# Carte_OPB.net
KiCad netlist of a schematic drawn in Altium Designer
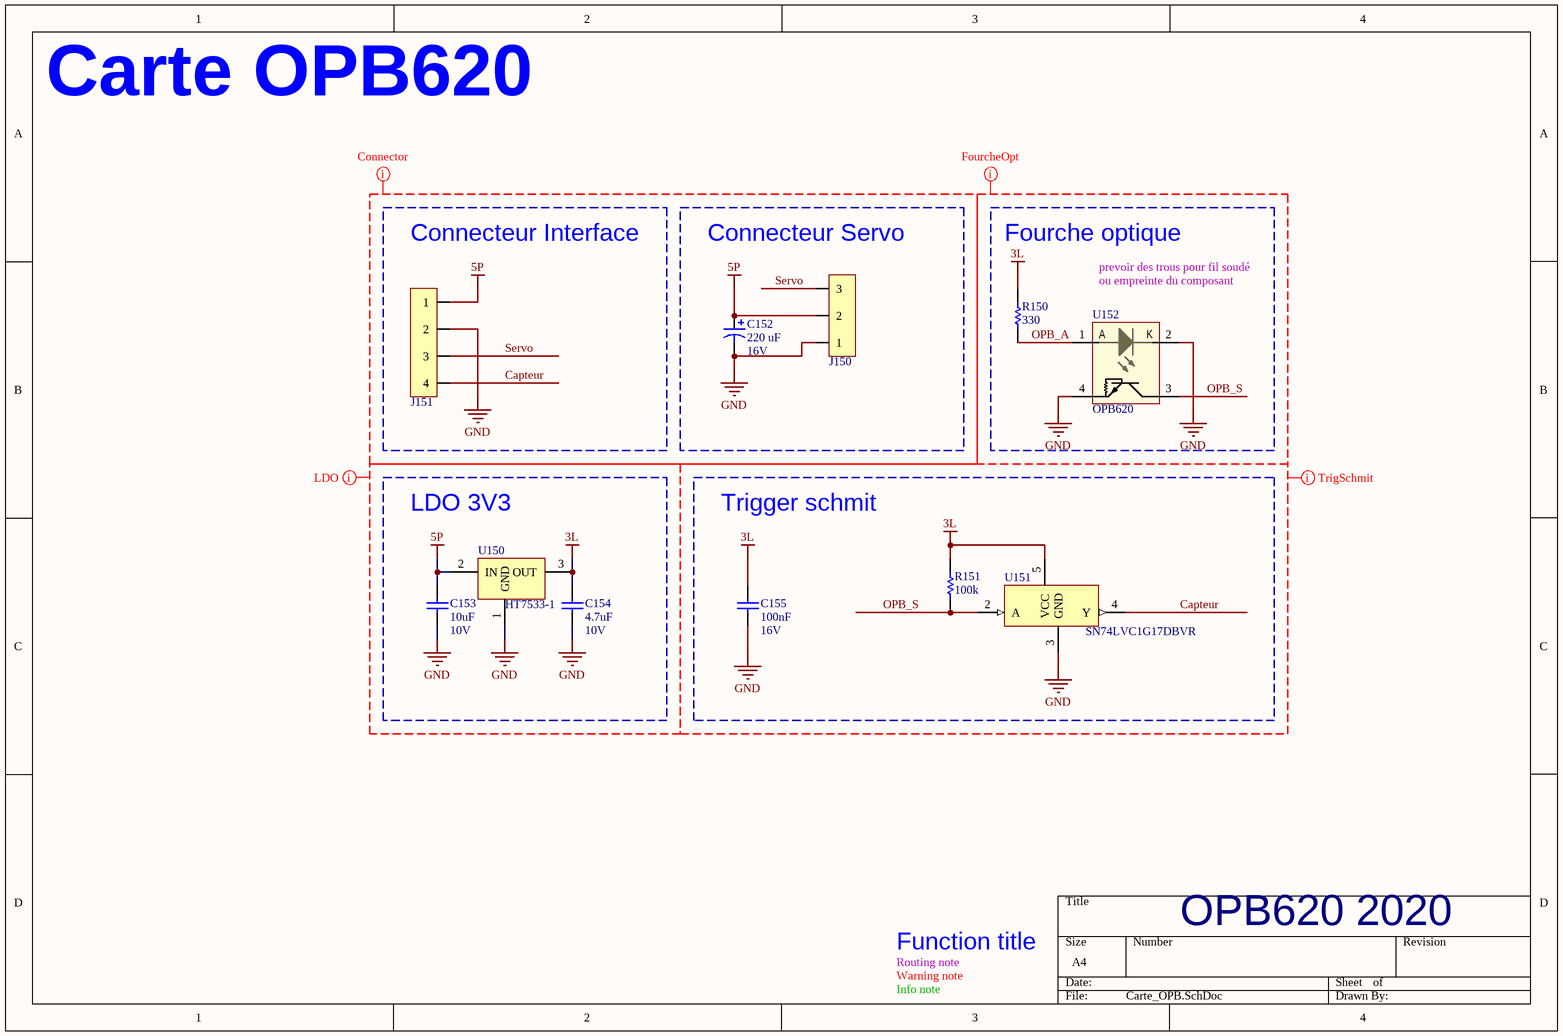
[diagram p0: Carte_OPB.SchDoc]

(export (version "E")
  (design (tool "Eeschema 10.0.6"))
  (components
    (comp (ref "C152")
      (value "220 uF")
      (footprint "WCAP-ATG8_6.3x11x2.5x0.5")
      (description "CAP Alu 220 UF 20% 16 V")
      (fields
        (field (name "MANUFACTURER") "Wurth Elektronik")
        (field (name "MANUFACTURER PART NUMBER") "860010373010")
        (field (name "RATEDVOLTAGE") "16V")
      )
      (libsource (lib "Condensateur") (part "WCAP-ATG8, 860010373010"))
    )
    (comp (ref "C153")
      (value "10uF")
      (footprint "WCAP-CSGP_0805, 2x1.25x1.25")
      (description "CAP CER 10uF 10V X7R 0805")
      (fields
        (field (name "RATEDVOLTAGE") "10V")
        (field (name "MANUFACTURER") "Wurth Elektronik")
        (field (name "MANUFACTURER PART NUMBER") "885012207026")
      )
      (libsource (lib "Condensateur") (part "WCAP-CSGP, 885012207026"))
    )
    (comp (ref "C154")
      (value "4.7uF")
      (footprint "WCAP-CSGP_0603, 1.6x0.8x0.8")
      (description "CAP CER 4.7UF 10V X5R 0603")
      (fields
        (field (name "RATEDVOLTAGE") "10V")
        (field (name "MANUFACTURER") "Wurth Elektronik")
        (field (name "MANUFACTURER PART NUMBER") "885012106012")
      )
      (libsource (lib "Condensateur") (part "WCAP-CSGP, 885012106012"))
    )
    (comp (ref "C155")
      (value "100nF")
      (footprint "WCAP-CSGP_0402, 1x0.5x0.5")
      (description "CAP CER 100nF 16V X7R 0402")
      (fields
        (field (name "RATEDVOLTAGE") "16V")
        (field (name "MANUFACTURER") "Wurth Elektronik")
        (field (name "MANUFACTURER PART NUMBER") "885012205037")
      )
      (libsource (lib "Condensateur") (part "WCAP-CSGP, 885012205037"))
    )
    (comp (ref "J150")
      (value "22-03-2031")
      (footprint "22-03-2031")
      (description "CONN HEADER VERT 3POS 2.54MM")
      (fields (field (name "MANUFACTURER") "MOLEX"))
      (libsource (lib "Connecteurs") (part "22-03-2031"))
    )
    (comp (ref "J151")
      (value "22-03-2041")
      (footprint "22-03-2041")
      (description "CONN HEADER VERT 4POS 2.54MM")
      (fields (field (name "MANUFACTURER") "MOLEX"))
      (libsource (lib "Connecteurs") (part "22-03-2041"))
    )
    (comp (ref "R150")
      (value "330")
      (footprint "RESC1005X04N")
      (description "RES SMD 330 OHM 1% 1/16W 0402")
      (fields (field (name "POWER") "63mW") (field (name "MANUFACTURER") "Yageo"))
      (libsource (lib "Resistance") (part "RC0402FR-07330RL"))
    )
    (comp (ref "R151")
      (value "100k")
      (footprint "RESC1005X04N")
      (description "RES SMD 100K OHM 1% 1/16W 0402")
      (fields (field (name "POWER") "63mW") (field (name "MANUFACTURER") "Yageo"))
      (libsource (lib "Resistance") (part "RC0402FR-07100KL"))
    )
    (comp (ref "U150")
      (value "HT7533-1")
      (footprint "SOT89-150P350X160-3N")
      (description "LDO 3.3V 100mA SOT89")
      (fields (field (name "MANUFACTURER") "Holtek"))
      (libsource (lib "Alimentation") (part "HT7533-1"))
    )
    (comp (ref "U151")
      (value "SN74LVC1G17DBVR")
      (footprint "SOT23_95P280X145-5N")
      (description "IC BUF NON-INVERT 5.5V SOT23-5")
      (fields (field (name "MANUFACTURER") "TEXAS INSTRUMENTS"))
      (libsource (lib "CI") (part "SN74LVC1G17DBVR"))
    )
    (comp (ref "U152")
      (value "OPB620")
      (footprint "OPB620")
      (description "SENSOR OPT SLOT TRANS W/RES PCB")
      (fields (field (name "MANUFACTURER") "TT ELECTRONICS"))
      (libsource (lib "Opto") (part "OPB620"))
    )
  )
  (nets
    (net (code "1") (name "/Capteur") (class "Default")
      (node (ref "J151") (pin "4") (pinfunction "4_4") (pintype "passive"))
      (node (ref "U151") (pin "4") (pinfunction "Y_4") (pintype "output"))
    )
    (net (code "2") (name "/OPB_A") (class "Default")
      (node (ref "R150") (pin "2") (pinfunction "2_2") (pintype "passive"))
      (node (ref "U152") (pin "1") (pinfunction "LED_A_1") (pintype "passive"))
    )
    (net (code "3") (name "/OPB_S") (class "Default")
      (node (ref "R151") (pin "1") (pinfunction "1_1") (pintype "passive"))
      (node (ref "U151") (pin "2") (pinfunction "A_2") (pintype "input"))
      (node (ref "U152") (pin "3") (pinfunction "NPN_C_3") (pintype "passive"))
    )
    (net (code "4") (name "/Servo") (class "Default")
      (node (ref "J150") (pin "3") (pinfunction "3_3") (pintype "passive"))
      (node (ref "J151") (pin "3") (pinfunction "3_3") (pintype "passive"))
    )
    (net (code "5") (name "3L") (class "Default")
      (node (ref "C154") (pin "1") (pinfunction "1_1") (pintype "passive"))
      (node (ref "C155") (pin "1") (pinfunction "1_1") (pintype "passive"))
      (node (ref "R150") (pin "1") (pinfunction "1_1") (pintype "passive"))
      (node (ref "R151") (pin "2") (pinfunction "2_2") (pintype "passive"))
      (node (ref "U150") (pin "3") (pinfunction "OUT_3") (pintype "power_in"))
      (node (ref "U151") (pin "5") (pinfunction "VCC_5") (pintype "power_in"))
    )
    (net (code "6") (name "5P") (class "Default")
      (node (ref "C152") (pin "1") (pinfunction "1_1") (pintype "passive"))
      (node (ref "C153") (pin "1") (pinfunction "1_1") (pintype "passive"))
      (node (ref "J150") (pin "2") (pinfunction "2_2") (pintype "passive"))
      (node (ref "J151") (pin "1") (pinfunction "1_1") (pintype "passive"))
      (node (ref "U150") (pin "2") (pinfunction "IN_2") (pintype "power_in"))
    )
    (net (code "7") (name "GND") (class "Default")
      (node (ref "C152") (pin "2") (pinfunction "2_2") (pintype "passive"))
      (node (ref "C153") (pin "2") (pinfunction "2_2") (pintype "passive"))
      (node (ref "C154") (pin "2") (pinfunction "2_2") (pintype "passive"))
      (node (ref "C155") (pin "2") (pinfunction "2_2") (pintype "passive"))
      (node (ref "J150") (pin "1") (pinfunction "1_1") (pintype "passive"))
      (node (ref "J151") (pin "2") (pinfunction "2_2") (pintype "passive"))
      (node (ref "U150") (pin "1") (pinfunction "GND_1") (pintype "power_in"))
      (node (ref "U151") (pin "3") (pinfunction "GND_3") (pintype "power_in"))
      (node (ref "U152") (pin "2") (pinfunction "LED_K_2") (pintype "passive"))
      (node (ref "U152") (pin "4") (pinfunction "NPN_E_4") (pintype "passive"))
    )
    (net (code "8") (name "unconnected-(U151-NC-Pad1)") (class "Default")
      (node (ref "U151") (pin "1") (pinfunction "NC_1") (pintype "passive"))
    )
  )
)
